# Hirose64-PlatingInterface.net
KiCad netlist of a schematic drawn in EAGLE
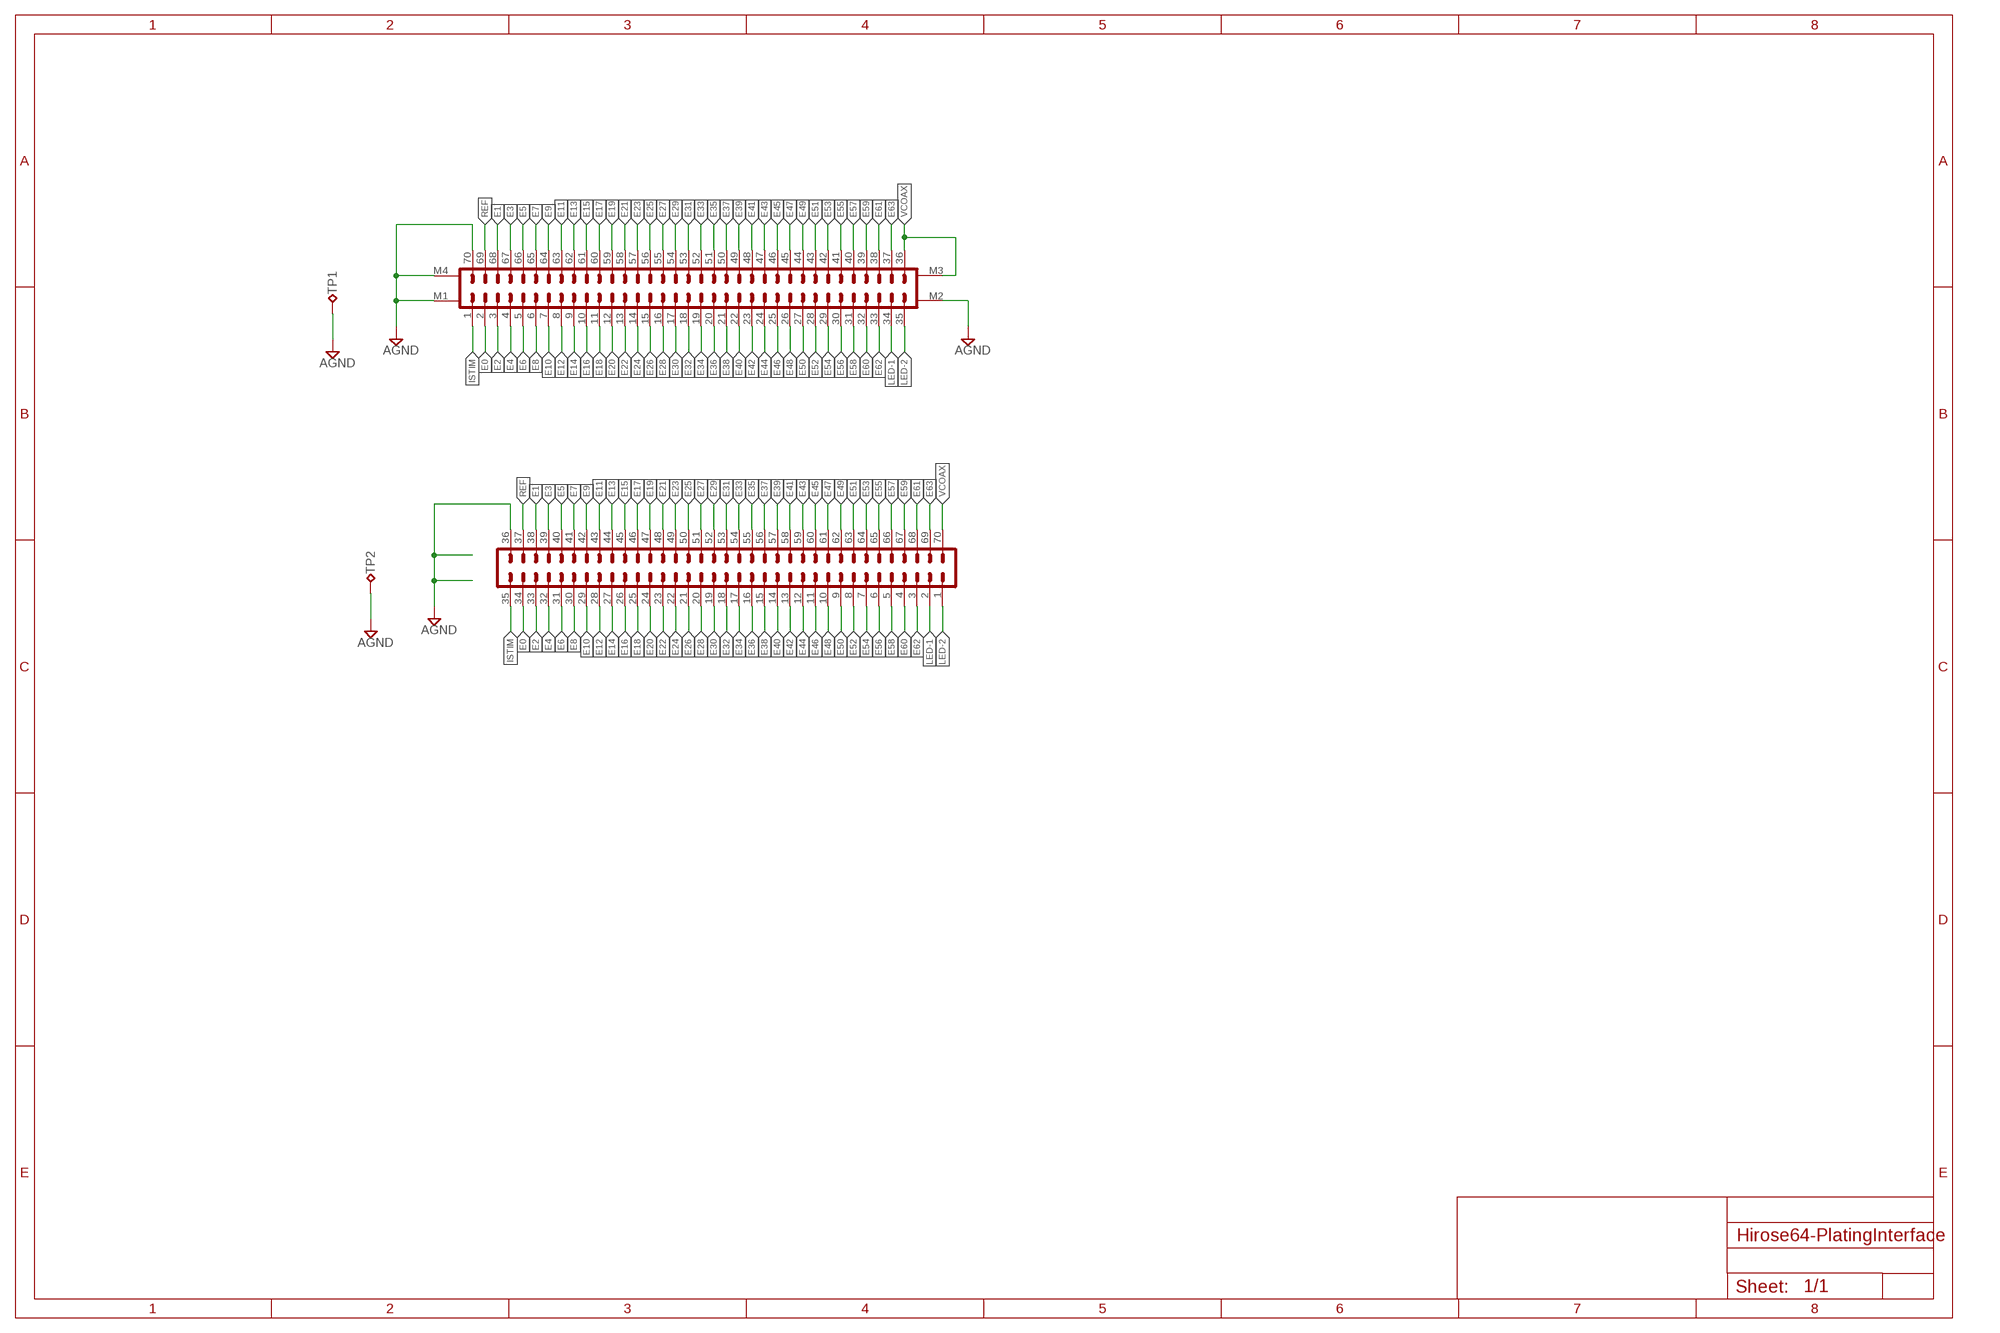
[diagram p0: schematic, sheet 1]

(export (version "E")
  (design (tool "Eeschema 10.0.6"))
  (components
    (comp (ref "J1")
      (value "DF40C-70DP-0.4V(51)")
      (footprint "eagle-import:DF40-70HEAD-LESS-SILK")
      (libsource (lib "eagle-import") (part "PINHD-2X35+4DF40-70HEAD-LESS-SILK"))
    )
    (comp (ref "J3")
      (value "DF40-REC")
      (footprint "eagle-import:DDF40-70REC-LRG")
      (libsource (lib "eagle-import") (part "PINHD-2X35_DF40REF-LRG"))
    )
    (comp (ref "TP1")
      (value "VCC")
      (footprint "eagle-import:TP07R")
      (libsource (lib "eagle-import") (part "TPTP07R"))
    )
    (comp (ref "TP2")
      (value "VCC")
      (footprint "eagle-import:TP07R")
      (libsource (lib "eagle-import") (part "TPTP07R"))
    )
  )
  (nets
    (net (code "1") (name "AGND") (class "Default")
      (node (ref "J1") (pin "70") (pinfunction "70_70") (pintype "bidirectional"))
      (node (ref "J1") (pin "M1") (pinfunction "M1_M1") (pintype "bidirectional"))
      (node (ref "J1") (pin "M2") (pinfunction "M2_M2") (pintype "bidirectional"))
      (node (ref "J1") (pin "M4") (pinfunction "M4_M4") (pintype "bidirectional"))
      (node (ref "J3") (pin "36") (pinfunction "36_36") (pintype "bidirectional"))
      (node (ref "TP1") (pin "TP") (pinfunction "TP_TP") (pintype "bidirectional"))
      (node (ref "TP2") (pin "TP") (pinfunction "TP_TP") (pintype "bidirectional"))
    )
    (net (code "2") (name "E0") (class "Default")
      (node (ref "J1") (pin "2") (pinfunction "2_2") (pintype "bidirectional"))
      (node (ref "J3") (pin "34") (pinfunction "34_34") (pintype "bidirectional"))
    )
    (net (code "3") (name "E1") (class "Default")
      (node (ref "J1") (pin "68") (pinfunction "68_68") (pintype "bidirectional"))
      (node (ref "J3") (pin "38") (pinfunction "38_38") (pintype "bidirectional"))
    )
    (net (code "4") (name "E2") (class "Default")
      (node (ref "J1") (pin "3") (pinfunction "3_3") (pintype "bidirectional"))
      (node (ref "J3") (pin "33") (pinfunction "33_33") (pintype "bidirectional"))
    )
    (net (code "5") (name "E3") (class "Default")
      (node (ref "J1") (pin "67") (pinfunction "67_67") (pintype "bidirectional"))
      (node (ref "J3") (pin "39") (pinfunction "39_39") (pintype "bidirectional"))
    )
    (net (code "6") (name "E4") (class "Default")
      (node (ref "J1") (pin "4") (pinfunction "4_4") (pintype "bidirectional"))
      (node (ref "J3") (pin "32") (pinfunction "32_32") (pintype "bidirectional"))
    )
    (net (code "7") (name "E5") (class "Default")
      (node (ref "J1") (pin "66") (pinfunction "66_66") (pintype "bidirectional"))
      (node (ref "J3") (pin "40") (pinfunction "40_40") (pintype "bidirectional"))
    )
    (net (code "8") (name "E6") (class "Default")
      (node (ref "J1") (pin "5") (pinfunction "5_5") (pintype "bidirectional"))
      (node (ref "J3") (pin "31") (pinfunction "31_31") (pintype "bidirectional"))
    )
    (net (code "9") (name "E7") (class "Default")
      (node (ref "J1") (pin "65") (pinfunction "65_65") (pintype "bidirectional"))
      (node (ref "J3") (pin "41") (pinfunction "41_41") (pintype "bidirectional"))
    )
    (net (code "10") (name "E8") (class "Default")
      (node (ref "J1") (pin "6") (pinfunction "6_6") (pintype "bidirectional"))
      (node (ref "J3") (pin "30") (pinfunction "30_30") (pintype "bidirectional"))
    )
    (net (code "11") (name "E9") (class "Default")
      (node (ref "J1") (pin "64") (pinfunction "64_64") (pintype "bidirectional"))
      (node (ref "J3") (pin "42") (pinfunction "42_42") (pintype "bidirectional"))
    )
    (net (code "12") (name "E10") (class "Default")
      (node (ref "J1") (pin "7") (pinfunction "7_7") (pintype "bidirectional"))
      (node (ref "J3") (pin "29") (pinfunction "29_29") (pintype "bidirectional"))
    )
    (net (code "13") (name "E11") (class "Default")
      (node (ref "J1") (pin "63") (pinfunction "63_63") (pintype "bidirectional"))
      (node (ref "J3") (pin "43") (pinfunction "43_43") (pintype "bidirectional"))
    )
    (net (code "14") (name "E12") (class "Default")
      (node (ref "J1") (pin "8") (pinfunction "8_8") (pintype "bidirectional"))
      (node (ref "J3") (pin "28") (pinfunction "28_28") (pintype "bidirectional"))
    )
    (net (code "15") (name "E13") (class "Default")
      (node (ref "J1") (pin "62") (pinfunction "62_62") (pintype "bidirectional"))
      (node (ref "J3") (pin "44") (pinfunction "44_44") (pintype "bidirectional"))
    )
    (net (code "16") (name "E14") (class "Default")
      (node (ref "J1") (pin "9") (pinfunction "9_9") (pintype "bidirectional"))
      (node (ref "J3") (pin "27") (pinfunction "27_27") (pintype "bidirectional"))
    )
    (net (code "17") (name "E15") (class "Default")
      (node (ref "J1") (pin "61") (pinfunction "61_61") (pintype "bidirectional"))
      (node (ref "J3") (pin "45") (pinfunction "45_45") (pintype "bidirectional"))
    )
    (net (code "18") (name "E16") (class "Default")
      (node (ref "J1") (pin "10") (pinfunction "10_10") (pintype "bidirectional"))
      (node (ref "J3") (pin "26") (pinfunction "26_26") (pintype "bidirectional"))
    )
    (net (code "19") (name "E17") (class "Default")
      (node (ref "J1") (pin "60") (pinfunction "60_60") (pintype "bidirectional"))
      (node (ref "J3") (pin "46") (pinfunction "46_46") (pintype "bidirectional"))
    )
    (net (code "20") (name "E18") (class "Default")
      (node (ref "J1") (pin "11") (pinfunction "11_11") (pintype "bidirectional"))
      (node (ref "J3") (pin "25") (pinfunction "25_25") (pintype "bidirectional"))
    )
    (net (code "21") (name "E19") (class "Default")
      (node (ref "J1") (pin "59") (pinfunction "59_59") (pintype "bidirectional"))
      (node (ref "J3") (pin "47") (pinfunction "47_47") (pintype "bidirectional"))
    )
    (net (code "22") (name "E20") (class "Default")
      (node (ref "J1") (pin "12") (pinfunction "12_12") (pintype "bidirectional"))
      (node (ref "J3") (pin "24") (pinfunction "24_24") (pintype "bidirectional"))
    )
    (net (code "23") (name "E21") (class "Default")
      (node (ref "J1") (pin "58") (pinfunction "58_58") (pintype "bidirectional"))
      (node (ref "J3") (pin "48") (pinfunction "48_48") (pintype "bidirectional"))
    )
    (net (code "24") (name "E22") (class "Default")
      (node (ref "J1") (pin "13") (pinfunction "13_13") (pintype "bidirectional"))
      (node (ref "J3") (pin "23") (pinfunction "23_23") (pintype "bidirectional"))
    )
    (net (code "25") (name "E23") (class "Default")
      (node (ref "J1") (pin "57") (pinfunction "57_57") (pintype "bidirectional"))
      (node (ref "J3") (pin "49") (pinfunction "49_49") (pintype "bidirectional"))
    )
    (net (code "26") (name "E24") (class "Default")
      (node (ref "J1") (pin "14") (pinfunction "14_14") (pintype "bidirectional"))
      (node (ref "J3") (pin "22") (pinfunction "22_22") (pintype "bidirectional"))
    )
    (net (code "27") (name "E25") (class "Default")
      (node (ref "J1") (pin "56") (pinfunction "56_56") (pintype "bidirectional"))
      (node (ref "J3") (pin "50") (pinfunction "50_50") (pintype "bidirectional"))
    )
    (net (code "28") (name "E26") (class "Default")
      (node (ref "J1") (pin "15") (pinfunction "15_15") (pintype "bidirectional"))
      (node (ref "J3") (pin "21") (pinfunction "21_21") (pintype "bidirectional"))
    )
    (net (code "29") (name "E27") (class "Default")
      (node (ref "J1") (pin "55") (pinfunction "55_55") (pintype "bidirectional"))
      (node (ref "J3") (pin "51") (pinfunction "51_51") (pintype "bidirectional"))
    )
    (net (code "30") (name "E28") (class "Default")
      (node (ref "J1") (pin "16") (pinfunction "16_16") (pintype "bidirectional"))
      (node (ref "J3") (pin "20") (pinfunction "20_20") (pintype "bidirectional"))
    )
    (net (code "31") (name "E29") (class "Default")
      (node (ref "J1") (pin "54") (pinfunction "54_54") (pintype "bidirectional"))
      (node (ref "J3") (pin "52") (pinfunction "52_52") (pintype "bidirectional"))
    )
    (net (code "32") (name "E30") (class "Default")
      (node (ref "J1") (pin "17") (pinfunction "17_17") (pintype "bidirectional"))
      (node (ref "J3") (pin "19") (pinfunction "19_19") (pintype "bidirectional"))
    )
    (net (code "33") (name "E31") (class "Default")
      (node (ref "J1") (pin "53") (pinfunction "53_53") (pintype "bidirectional"))
      (node (ref "J3") (pin "53") (pinfunction "53_53") (pintype "bidirectional"))
    )
    (net (code "34") (name "E32") (class "Default")
      (node (ref "J1") (pin "18") (pinfunction "18_18") (pintype "bidirectional"))
      (node (ref "J3") (pin "18") (pinfunction "18_18") (pintype "bidirectional"))
    )
    (net (code "35") (name "E33") (class "Default")
      (node (ref "J1") (pin "52") (pinfunction "52_52") (pintype "bidirectional"))
      (node (ref "J3") (pin "54") (pinfunction "54_54") (pintype "bidirectional"))
    )
    (net (code "36") (name "E34") (class "Default")
      (node (ref "J1") (pin "19") (pinfunction "19_19") (pintype "bidirectional"))
      (node (ref "J3") (pin "17") (pinfunction "17_17") (pintype "bidirectional"))
    )
    (net (code "37") (name "E35") (class "Default")
      (node (ref "J1") (pin "51") (pinfunction "51_51") (pintype "bidirectional"))
      (node (ref "J3") (pin "55") (pinfunction "55_55") (pintype "bidirectional"))
    )
    (net (code "38") (name "E36") (class "Default")
      (node (ref "J1") (pin "20") (pinfunction "20_20") (pintype "bidirectional"))
      (node (ref "J3") (pin "16") (pinfunction "16_16") (pintype "bidirectional"))
    )
    (net (code "39") (name "E37") (class "Default")
      (node (ref "J1") (pin "50") (pinfunction "50_50") (pintype "bidirectional"))
      (node (ref "J3") (pin "56") (pinfunction "56_56") (pintype "bidirectional"))
    )
    (net (code "40") (name "E38") (class "Default")
      (node (ref "J1") (pin "21") (pinfunction "21_21") (pintype "bidirectional"))
      (node (ref "J3") (pin "15") (pinfunction "15_15") (pintype "bidirectional"))
    )
    (net (code "41") (name "E39") (class "Default")
      (node (ref "J1") (pin "49") (pinfunction "49_49") (pintype "bidirectional"))
      (node (ref "J3") (pin "57") (pinfunction "57_57") (pintype "bidirectional"))
    )
    (net (code "42") (name "E40") (class "Default")
      (node (ref "J1") (pin "22") (pinfunction "22_22") (pintype "bidirectional"))
      (node (ref "J3") (pin "14") (pinfunction "14_14") (pintype "bidirectional"))
    )
    (net (code "43") (name "E41") (class "Default")
      (node (ref "J1") (pin "48") (pinfunction "48_48") (pintype "bidirectional"))
      (node (ref "J3") (pin "58") (pinfunction "58_58") (pintype "bidirectional"))
    )
    (net (code "44") (name "E42") (class "Default")
      (node (ref "J1") (pin "23") (pinfunction "23_23") (pintype "bidirectional"))
      (node (ref "J3") (pin "13") (pinfunction "13_13") (pintype "bidirectional"))
    )
    (net (code "45") (name "E43") (class "Default")
      (node (ref "J1") (pin "47") (pinfunction "47_47") (pintype "bidirectional"))
      (node (ref "J3") (pin "59") (pinfunction "59_59") (pintype "bidirectional"))
    )
    (net (code "46") (name "E44") (class "Default")
      (node (ref "J1") (pin "24") (pinfunction "24_24") (pintype "bidirectional"))
      (node (ref "J3") (pin "12") (pinfunction "12_12") (pintype "bidirectional"))
    )
    (net (code "47") (name "E45") (class "Default")
      (node (ref "J1") (pin "46") (pinfunction "46_46") (pintype "bidirectional"))
      (node (ref "J3") (pin "60") (pinfunction "60_60") (pintype "bidirectional"))
    )
    (net (code "48") (name "E46") (class "Default")
      (node (ref "J1") (pin "25") (pinfunction "25_25") (pintype "bidirectional"))
      (node (ref "J3") (pin "11") (pinfunction "11_11") (pintype "bidirectional"))
    )
    (net (code "49") (name "E47") (class "Default")
      (node (ref "J1") (pin "45") (pinfunction "45_45") (pintype "bidirectional"))
      (node (ref "J3") (pin "61") (pinfunction "61_61") (pintype "bidirectional"))
    )
    (net (code "50") (name "E48") (class "Default")
      (node (ref "J1") (pin "26") (pinfunction "26_26") (pintype "bidirectional"))
      (node (ref "J3") (pin "10") (pinfunction "10_10") (pintype "bidirectional"))
    )
    (net (code "51") (name "E49") (class "Default")
      (node (ref "J1") (pin "44") (pinfunction "44_44") (pintype "bidirectional"))
      (node (ref "J3") (pin "62") (pinfunction "62_62") (pintype "bidirectional"))
    )
    (net (code "52") (name "E50") (class "Default")
      (node (ref "J1") (pin "27") (pinfunction "27_27") (pintype "bidirectional"))
      (node (ref "J3") (pin "9") (pinfunction "9_9") (pintype "bidirectional"))
    )
    (net (code "53") (name "E51") (class "Default")
      (node (ref "J1") (pin "43") (pinfunction "43_43") (pintype "bidirectional"))
      (node (ref "J3") (pin "63") (pinfunction "63_63") (pintype "bidirectional"))
    )
    (net (code "54") (name "E52") (class "Default")
      (node (ref "J1") (pin "28") (pinfunction "28_28") (pintype "bidirectional"))
      (node (ref "J3") (pin "8") (pinfunction "8_8") (pintype "bidirectional"))
    )
    (net (code "55") (name "E53") (class "Default")
      (node (ref "J1") (pin "42") (pinfunction "42_42") (pintype "bidirectional"))
      (node (ref "J3") (pin "64") (pinfunction "64_64") (pintype "bidirectional"))
    )
    (net (code "56") (name "E54") (class "Default")
      (node (ref "J1") (pin "29") (pinfunction "29_29") (pintype "bidirectional"))
      (node (ref "J3") (pin "7") (pinfunction "7_7") (pintype "bidirectional"))
    )
    (net (code "57") (name "E55") (class "Default")
      (node (ref "J1") (pin "41") (pinfunction "41_41") (pintype "bidirectional"))
      (node (ref "J3") (pin "65") (pinfunction "65_65") (pintype "bidirectional"))
    )
    (net (code "58") (name "E56") (class "Default")
      (node (ref "J1") (pin "30") (pinfunction "30_30") (pintype "bidirectional"))
      (node (ref "J3") (pin "6") (pinfunction "6_6") (pintype "bidirectional"))
    )
    (net (code "59") (name "E57") (class "Default")
      (node (ref "J1") (pin "40") (pinfunction "40_40") (pintype "bidirectional"))
      (node (ref "J3") (pin "66") (pinfunction "66_66") (pintype "bidirectional"))
    )
    (net (code "60") (name "E58") (class "Default")
      (node (ref "J1") (pin "31") (pinfunction "31_31") (pintype "bidirectional"))
      (node (ref "J3") (pin "5") (pinfunction "5_5") (pintype "bidirectional"))
    )
    (net (code "61") (name "E59") (class "Default")
      (node (ref "J1") (pin "39") (pinfunction "39_39") (pintype "bidirectional"))
      (node (ref "J3") (pin "67") (pinfunction "67_67") (pintype "bidirectional"))
    )
    (net (code "62") (name "E60") (class "Default")
      (node (ref "J1") (pin "32") (pinfunction "32_32") (pintype "bidirectional"))
      (node (ref "J3") (pin "4") (pinfunction "4_4") (pintype "bidirectional"))
    )
    (net (code "63") (name "E61") (class "Default")
      (node (ref "J1") (pin "38") (pinfunction "38_38") (pintype "bidirectional"))
      (node (ref "J3") (pin "68") (pinfunction "68_68") (pintype "bidirectional"))
    )
    (net (code "64") (name "E62") (class "Default")
      (node (ref "J1") (pin "33") (pinfunction "33_33") (pintype "bidirectional"))
      (node (ref "J3") (pin "3") (pinfunction "3_3") (pintype "bidirectional"))
    )
    (net (code "65") (name "E63") (class "Default")
      (node (ref "J1") (pin "37") (pinfunction "37_37") (pintype "bidirectional"))
      (node (ref "J3") (pin "69") (pinfunction "69_69") (pintype "bidirectional"))
    )
    (net (code "66") (name "ISTIM") (class "Default")
      (node (ref "J1") (pin "1") (pinfunction "1_1") (pintype "bidirectional"))
      (node (ref "J3") (pin "35") (pinfunction "35_35") (pintype "bidirectional"))
    )
    (net (code "67") (name "LED-1") (class "Default")
      (node (ref "J1") (pin "34") (pinfunction "34_34") (pintype "bidirectional"))
      (node (ref "J3") (pin "2") (pinfunction "2_2") (pintype "bidirectional"))
    )
    (net (code "68") (name "LED-2") (class "Default")
      (node (ref "J1") (pin "35") (pinfunction "35_35") (pintype "bidirectional"))
      (node (ref "J3") (pin "1") (pinfunction "1_1") (pintype "bidirectional"))
    )
    (net (code "69") (name "REF") (class "Default")
      (node (ref "J1") (pin "69") (pinfunction "69_69") (pintype "bidirectional"))
      (node (ref "J3") (pin "37") (pinfunction "37_37") (pintype "bidirectional"))
    )
    (net (code "70") (name "VCOAX") (class "Default")
      (node (ref "J1") (pin "36") (pinfunction "36_36") (pintype "bidirectional"))
      (node (ref "J1") (pin "M3") (pinfunction "M3_M3") (pintype "bidirectional"))
      (node (ref "J3") (pin "70") (pinfunction "70_70") (pintype "bidirectional"))
    )
  )
)
